# B2B_connectors.net
KiCad netlist of a schematic drawn in Altium Designer
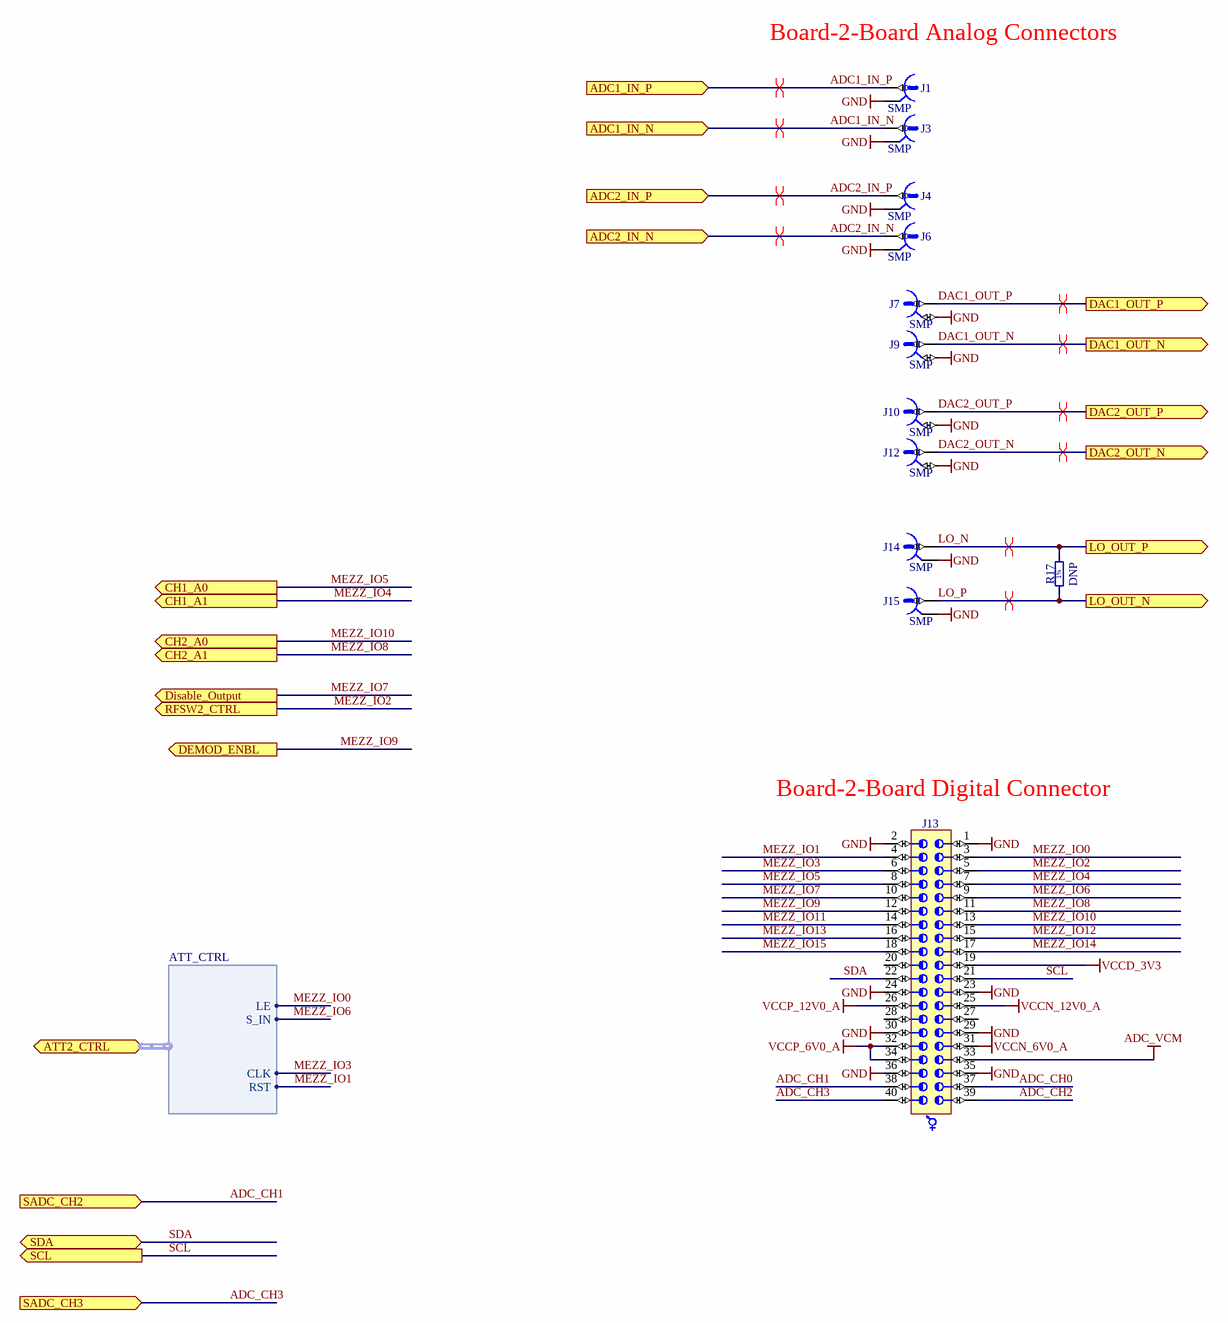
[diagram p0: B2B_connectors .SchDoc]

(export (version "E")
  (design (tool "Eeschema 10.0.6"))
  (components
    (comp (ref "J1")
      (value "SMP")
      (footprint "AMPHENOL_SMP-MSLD-PCT-10")
      (description "50 Ohms, SMP Surface/THT Mount Plug, Limited Detent")
      (fields
        (field (name "PART NUMBER") "AMPHENOL_SMP-MSLD-PCT-10")
        (field (name "MANUFACTURER") "AMPHENOL")
        (field (name "AUTHOR") "GK")
      )
      (libsource (lib "") (part "CON_SMP-MSLD-PCT-10_1"))
    )
    (comp (ref "J3")
      (value "SMP")
      (footprint "AMPHENOL_SMP-MSLD-PCT-10")
      (description "50 Ohms, SMP Surface/THT Mount Plug, Limited Detent")
      (fields
        (field (name "PART NUMBER") "AMPHENOL_SMP-MSLD-PCT-10")
        (field (name "MANUFACTURER") "AMPHENOL")
        (field (name "AUTHOR") "GK")
      )
      (libsource (lib "") (part "CON_SMP-MSLD-PCT-10_1"))
    )
    (comp (ref "J4")
      (value "SMP")
      (footprint "AMPHENOL_SMP-MSLD-PCT-10")
      (description "50 Ohms, SMP Surface/THT Mount Plug, Limited Detent")
      (fields
        (field (name "PART NUMBER") "AMPHENOL_SMP-MSLD-PCT-10")
        (field (name "MANUFACTURER") "AMPHENOL")
        (field (name "AUTHOR") "GK")
      )
      (libsource (lib "") (part "CON_SMP-MSLD-PCT-10_1"))
    )
    (comp (ref "J6")
      (value "SMP")
      (footprint "AMPHENOL_SMP-MSLD-PCT-10")
      (description "50 Ohms, SMP Surface/THT Mount Plug, Limited Detent")
      (fields
        (field (name "PART NUMBER") "AMPHENOL_SMP-MSLD-PCT-10")
        (field (name "MANUFACTURER") "AMPHENOL")
        (field (name "AUTHOR") "GK")
      )
      (libsource (lib "") (part "CON_SMP-MSLD-PCT-10_1"))
    )
    (comp (ref "J7")
      (value "SMP")
      (footprint "MOLEX_85305-0232")
      (fields
        (field (name "PART NUMBER") "MOLEX_85305-0232")
        (field (name "MANUFACTURER") "MOLEX")
        (field (name "MANUFACTURER PART NUMBER") "85305-0232")
        (field (name "AUTHOR") "CERN DEM JMW")
      )
      (libsource (lib "Connectors") (part "Coax_1Male_1Shield"))
    )
    (comp (ref "J9")
      (value "SMP")
      (footprint "MOLEX_85305-0232")
      (fields
        (field (name "PART NUMBER") "MOLEX_85305-0232")
        (field (name "MANUFACTURER") "MOLEX")
        (field (name "MANUFACTURER PART NUMBER") "85305-0232")
        (field (name "AUTHOR") "CERN DEM JMW")
      )
      (libsource (lib "Connectors") (part "Coax_1Male_1Shield"))
    )
    (comp (ref "J10")
      (value "SMP")
      (footprint "MOLEX_85305-0232")
      (fields
        (field (name "PART NUMBER") "MOLEX_85305-0232")
        (field (name "MANUFACTURER") "MOLEX")
        (field (name "MANUFACTURER PART NUMBER") "85305-0232")
        (field (name "AUTHOR") "CERN DEM JMW")
      )
      (libsource (lib "Connectors") (part "Coax_1Male_1Shield"))
    )
    (comp (ref "J12")
      (value "SMP")
      (footprint "MOLEX_85305-0232")
      (fields
        (field (name "PART NUMBER") "MOLEX_85305-0232")
        (field (name "MANUFACTURER") "MOLEX")
        (field (name "MANUFACTURER PART NUMBER") "85305-0232")
        (field (name "AUTHOR") "CERN DEM JMW")
      )
      (libsource (lib "Connectors") (part "Coax_1Male_1Shield"))
    )
    (comp (ref "J13")
      (value "~")
      (footprint "SAMTEC_LSS-120-02-L-DV-A")
      (fields
        (field (name "PART NUMBER") "SAMTEC_LSS-120-02-L-DV-A")
        (field (name "MANUFACTURER") "SAMTEC")
        (field (name "MANUFACTURER PART NUMBER") "LSS-120-02-L-DV-A")
        (field (name "AUTHOR") "CERN DEM JMW")
      )
      (libsource (lib "LIBRARY_SCH") (part "CON_SAMTEC_LSS-120-02-L-DV-A"))
    )
    (comp (ref "J14")
      (value "SMP")
      (footprint "AMPHENOL_SMP-MSLD-PCT-10")
      (description "50 Ohms, SMP Surface/THT Mount Plug, Limited Detent")
      (fields
        (field (name "PART NUMBER") "AMPHENOL_SMP-MSLD-PCT-10")
        (field (name "MANUFACTURER") "AMPHENOL")
        (field (name "AUTHOR") "GK")
      )
      (libsource (lib "LIBRARY_SCH") (part "CON_SMP-MSLD-PCT-10"))
    )
    (comp (ref "J15")
      (value "SMP")
      (footprint "AMPHENOL_SMP-MSLD-PCT-10")
      (description "50 Ohms, SMP Surface/THT Mount Plug, Limited Detent")
      (fields
        (field (name "PART NUMBER") "AMPHENOL_SMP-MSLD-PCT-10")
        (field (name "MANUFACTURER") "AMPHENOL")
        (field (name "AUTHOR") "GK")
      )
      (libsource (lib "LIBRARY_SCH") (part "CON_SMP-MSLD-PCT-10"))
    )
    (comp (ref "R17")
      (value "DNP")
      (footprint "RESC1005X40N")
      (description "Resistor - 1%")
      (fields
        (field (name "PART NUMBER") "R0402_100R_1%_0.0625W_100PPM")
        (field (name "POWER") "0.0625W")
        (field (name "AUTHOR") "CERN DEM JLC")
      )
      (libsource (lib "Resistors") (part "Resistor - 1%"))
    )
  )
  (nets
    (net (code "2") (name "/ADC1_IN_N") (class "Default")
      (node (ref "J3") (pin "1") (pinfunction "1_1") (pintype "bidirectional"))
    )
    (net (code "3") (name "/ADC1_IN_P") (class "Default")
      (node (ref "J1") (pin "1") (pinfunction "1_1") (pintype "bidirectional"))
    )
    (net (code "4") (name "/ADC2_IN_N") (class "Default")
      (node (ref "J6") (pin "1") (pinfunction "1_1") (pintype "bidirectional"))
    )
    (net (code "5") (name "/ADC2_IN_P") (class "Default")
      (node (ref "J4") (pin "1") (pinfunction "1_1") (pintype "bidirectional"))
    )
    (net (code "6") (name "/ADC_CH0") (class "Default")
      (node (ref "J13") (pin "37") (pinfunction "37_37") (pintype "bidirectional"))
    )
    (net (code "7") (name "/ADC_CH1") (class "Default")
      (node (ref "J13") (pin "38") (pinfunction "38_38") (pintype "bidirectional"))
    )
    (net (code "8") (name "/ADC_CH2") (class "Default")
      (node (ref "J13") (pin "39") (pinfunction "39_39") (pintype "bidirectional"))
    )
    (net (code "9") (name "/ADC_CH3") (class "Default")
      (node (ref "J13") (pin "40") (pinfunction "40_40") (pintype "bidirectional"))
    )
    (net (code "10") (name "/DAC1_OUT_N") (class "Default")
      (node (ref "J9") (pin "1") (pinfunction "1_1") (pintype "bidirectional"))
    )
    (net (code "11") (name "/DAC1_OUT_P") (class "Default")
      (node (ref "J7") (pin "1") (pinfunction "1_1") (pintype "bidirectional"))
    )
    (net (code "12") (name "/DAC2_OUT_N") (class "Default")
      (node (ref "J12") (pin "1") (pinfunction "1_1") (pintype "bidirectional"))
    )
    (net (code "13") (name "/DAC2_OUT_P") (class "Default")
      (node (ref "J10") (pin "1") (pinfunction "1_1") (pintype "bidirectional"))
    )
    (net (code "14") (name "/LO_N") (class "Default")
      (node (ref "J14") (pin "1") (pinfunction "1_1") (pintype "bidirectional"))
      (node (ref "R17") (pin "2") (pinfunction "2_2") (pintype "passive"))
    )
    (net (code "15") (name "/LO_P") (class "Default")
      (node (ref "J15") (pin "1") (pinfunction "1_1") (pintype "bidirectional"))
      (node (ref "R17") (pin "1") (pinfunction "1_1") (pintype "passive"))
    )
    (net (code "16") (name "/MEZZ_IO0") (class "Default")
      (node (ref "J13") (pin "3") (pinfunction "3_3") (pintype "bidirectional"))
    )
    (net (code "17") (name "/MEZZ_IO1") (class "Default")
      (node (ref "J13") (pin "4") (pinfunction "4_4") (pintype "bidirectional"))
    )
    (net (code "18") (name "/MEZZ_IO2") (class "Default")
      (node (ref "J13") (pin "5") (pinfunction "5_5") (pintype "bidirectional"))
    )
    (net (code "19") (name "/MEZZ_IO3") (class "Default")
      (node (ref "J13") (pin "6") (pinfunction "6_6") (pintype "bidirectional"))
    )
    (net (code "20") (name "/MEZZ_IO4") (class "Default")
      (node (ref "J13") (pin "7") (pinfunction "7_7") (pintype "bidirectional"))
    )
    (net (code "21") (name "/MEZZ_IO5") (class "Default")
      (node (ref "J13") (pin "8") (pinfunction "8_8") (pintype "bidirectional"))
    )
    (net (code "22") (name "/MEZZ_IO6") (class "Default")
      (node (ref "J13") (pin "9") (pinfunction "9_9") (pintype "bidirectional"))
    )
    (net (code "23") (name "/MEZZ_IO7") (class "Default")
      (node (ref "J13") (pin "10") (pinfunction "10_10") (pintype "bidirectional"))
    )
    (net (code "24") (name "/MEZZ_IO8") (class "Default")
      (node (ref "J13") (pin "11") (pinfunction "11_11") (pintype "bidirectional"))
    )
    (net (code "25") (name "/MEZZ_IO9") (class "Default")
      (node (ref "J13") (pin "12") (pinfunction "12_12") (pintype "bidirectional"))
    )
    (net (code "26") (name "/MEZZ_IO10") (class "Default")
      (node (ref "J13") (pin "13") (pinfunction "13_13") (pintype "bidirectional"))
    )
    (net (code "27") (name "/MEZZ_IO11") (class "Default")
      (node (ref "J13") (pin "14") (pinfunction "14_14") (pintype "bidirectional"))
    )
    (net (code "28") (name "/MEZZ_IO12") (class "Default")
      (node (ref "J13") (pin "15") (pinfunction "15_15") (pintype "bidirectional"))
    )
    (net (code "29") (name "/MEZZ_IO13") (class "Default")
      (node (ref "J13") (pin "16") (pinfunction "16_16") (pintype "bidirectional"))
    )
    (net (code "30") (name "/MEZZ_IO14") (class "Default")
      (node (ref "J13") (pin "17") (pinfunction "17_17") (pintype "bidirectional"))
    )
    (net (code "31") (name "/MEZZ_IO15") (class "Default")
      (node (ref "J13") (pin "18") (pinfunction "18_18") (pintype "bidirectional"))
    )
    (net (code "32") (name "/SCL") (class "Default")
      (node (ref "J13") (pin "21") (pinfunction "21_21") (pintype "bidirectional"))
    )
    (net (code "33") (name "/SDA") (class "Default")
      (node (ref "J13") (pin "22") (pinfunction "22_22") (pintype "bidirectional"))
    )
    (net (code "35") (name "ADC_VCM") (class "Default")
      (node (ref "J13") (pin "33") (pinfunction "33_33") (pintype "bidirectional"))
    )
    (net (code "36") (name "GND") (class "Default")
      (node (ref "J1") (pin "2") (pinfunction "2_2") (pintype "passive"))
      (node (ref "J10") (pin "2") (pinfunction "2_2") (pintype "bidirectional"))
      (node (ref "J12") (pin "2") (pinfunction "2_2") (pintype "bidirectional"))
      (node (ref "J13") (pin "1") (pinfunction "1_1") (pintype "bidirectional"))
      (node (ref "J13") (pin "2") (pinfunction "2_2") (pintype "bidirectional"))
      (node (ref "J13") (pin "23") (pinfunction "23_23") (pintype "bidirectional"))
      (node (ref "J13") (pin "24") (pinfunction "24_24") (pintype "bidirectional"))
      (node (ref "J13") (pin "29") (pinfunction "29_29") (pintype "bidirectional"))
      (node (ref "J13") (pin "30") (pinfunction "30_30") (pintype "bidirectional"))
      (node (ref "J13") (pin "35") (pinfunction "35_35") (pintype "bidirectional"))
      (node (ref "J13") (pin "36") (pinfunction "36_36") (pintype "bidirectional"))
      (node (ref "J14") (pin "2") (pinfunction "2_2") (pintype "passive"))
      (node (ref "J15") (pin "2") (pinfunction "2_2") (pintype "passive"))
      (node (ref "J3") (pin "2") (pinfunction "2_2") (pintype "passive"))
      (node (ref "J4") (pin "2") (pinfunction "2_2") (pintype "passive"))
      (node (ref "J6") (pin "2") (pinfunction "2_2") (pintype "passive"))
      (node (ref "J7") (pin "2") (pinfunction "2_2") (pintype "bidirectional"))
      (node (ref "J9") (pin "2") (pinfunction "2_2") (pintype "bidirectional"))
    )
    (net (code "37") (name "VCCD_3V3") (class "Default")
      (node (ref "J13") (pin "19") (pinfunction "19_19") (pintype "bidirectional"))
    )
    (net (code "38") (name "VCCN_6V0_A") (class "Default")
      (node (ref "J13") (pin "31") (pinfunction "31_31") (pintype "bidirectional"))
    )
    (net (code "39") (name "VCCN_12V0_A") (class "Default")
      (node (ref "J13") (pin "25") (pinfunction "25_25") (pintype "bidirectional"))
    )
    (net (code "40") (name "VCCP_6V0_A") (class "Default")
      (node (ref "J13") (pin "32") (pinfunction "32_32") (pintype "bidirectional"))
      (node (ref "J13") (pin "34") (pinfunction "34_34") (pintype "bidirectional"))
    )
    (net (code "41") (name "VCCP_12V0_A") (class "Default")
      (node (ref "J13") (pin "26") (pinfunction "26_26") (pintype "bidirectional"))
    )
    (net (code "42") (name "unconnected-(J13-Pad20)") (class "Default")
      (node (ref "J13") (pin "20") (pinfunction "20_20") (pintype "bidirectional"))
    )
    (net (code "43") (name "unconnected-(J13-Pad27)") (class "Default")
      (node (ref "J13") (pin "27") (pinfunction "27_27") (pintype "bidirectional"))
    )
    (net (code "44") (name "unconnected-(J13-Pad28)") (class "Default")
      (node (ref "J13") (pin "28") (pinfunction "28_28") (pintype "bidirectional"))
    )
  )
)
